# DMRobotSchematic.net
KiCad netlist of a schematic drawn in Altium Designer
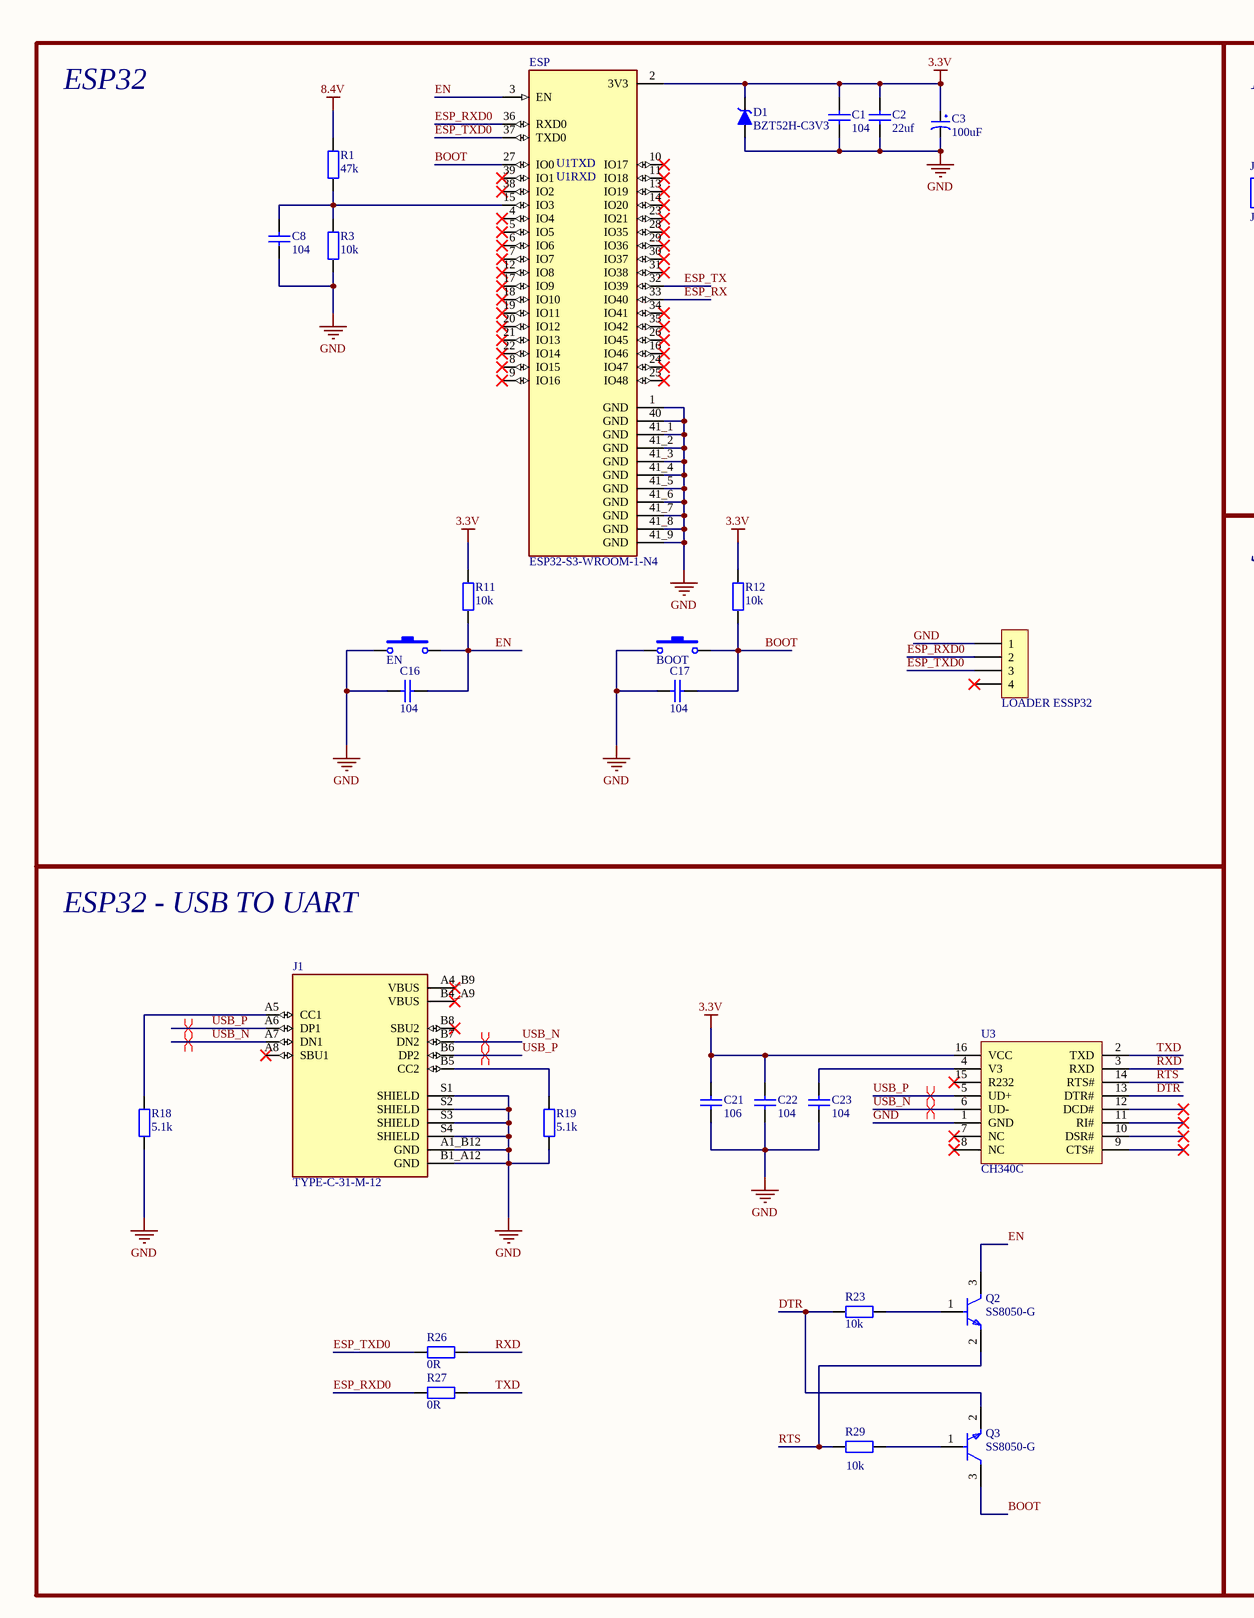
[diagram p0: DMRobotSchematic.SchDoc, left]
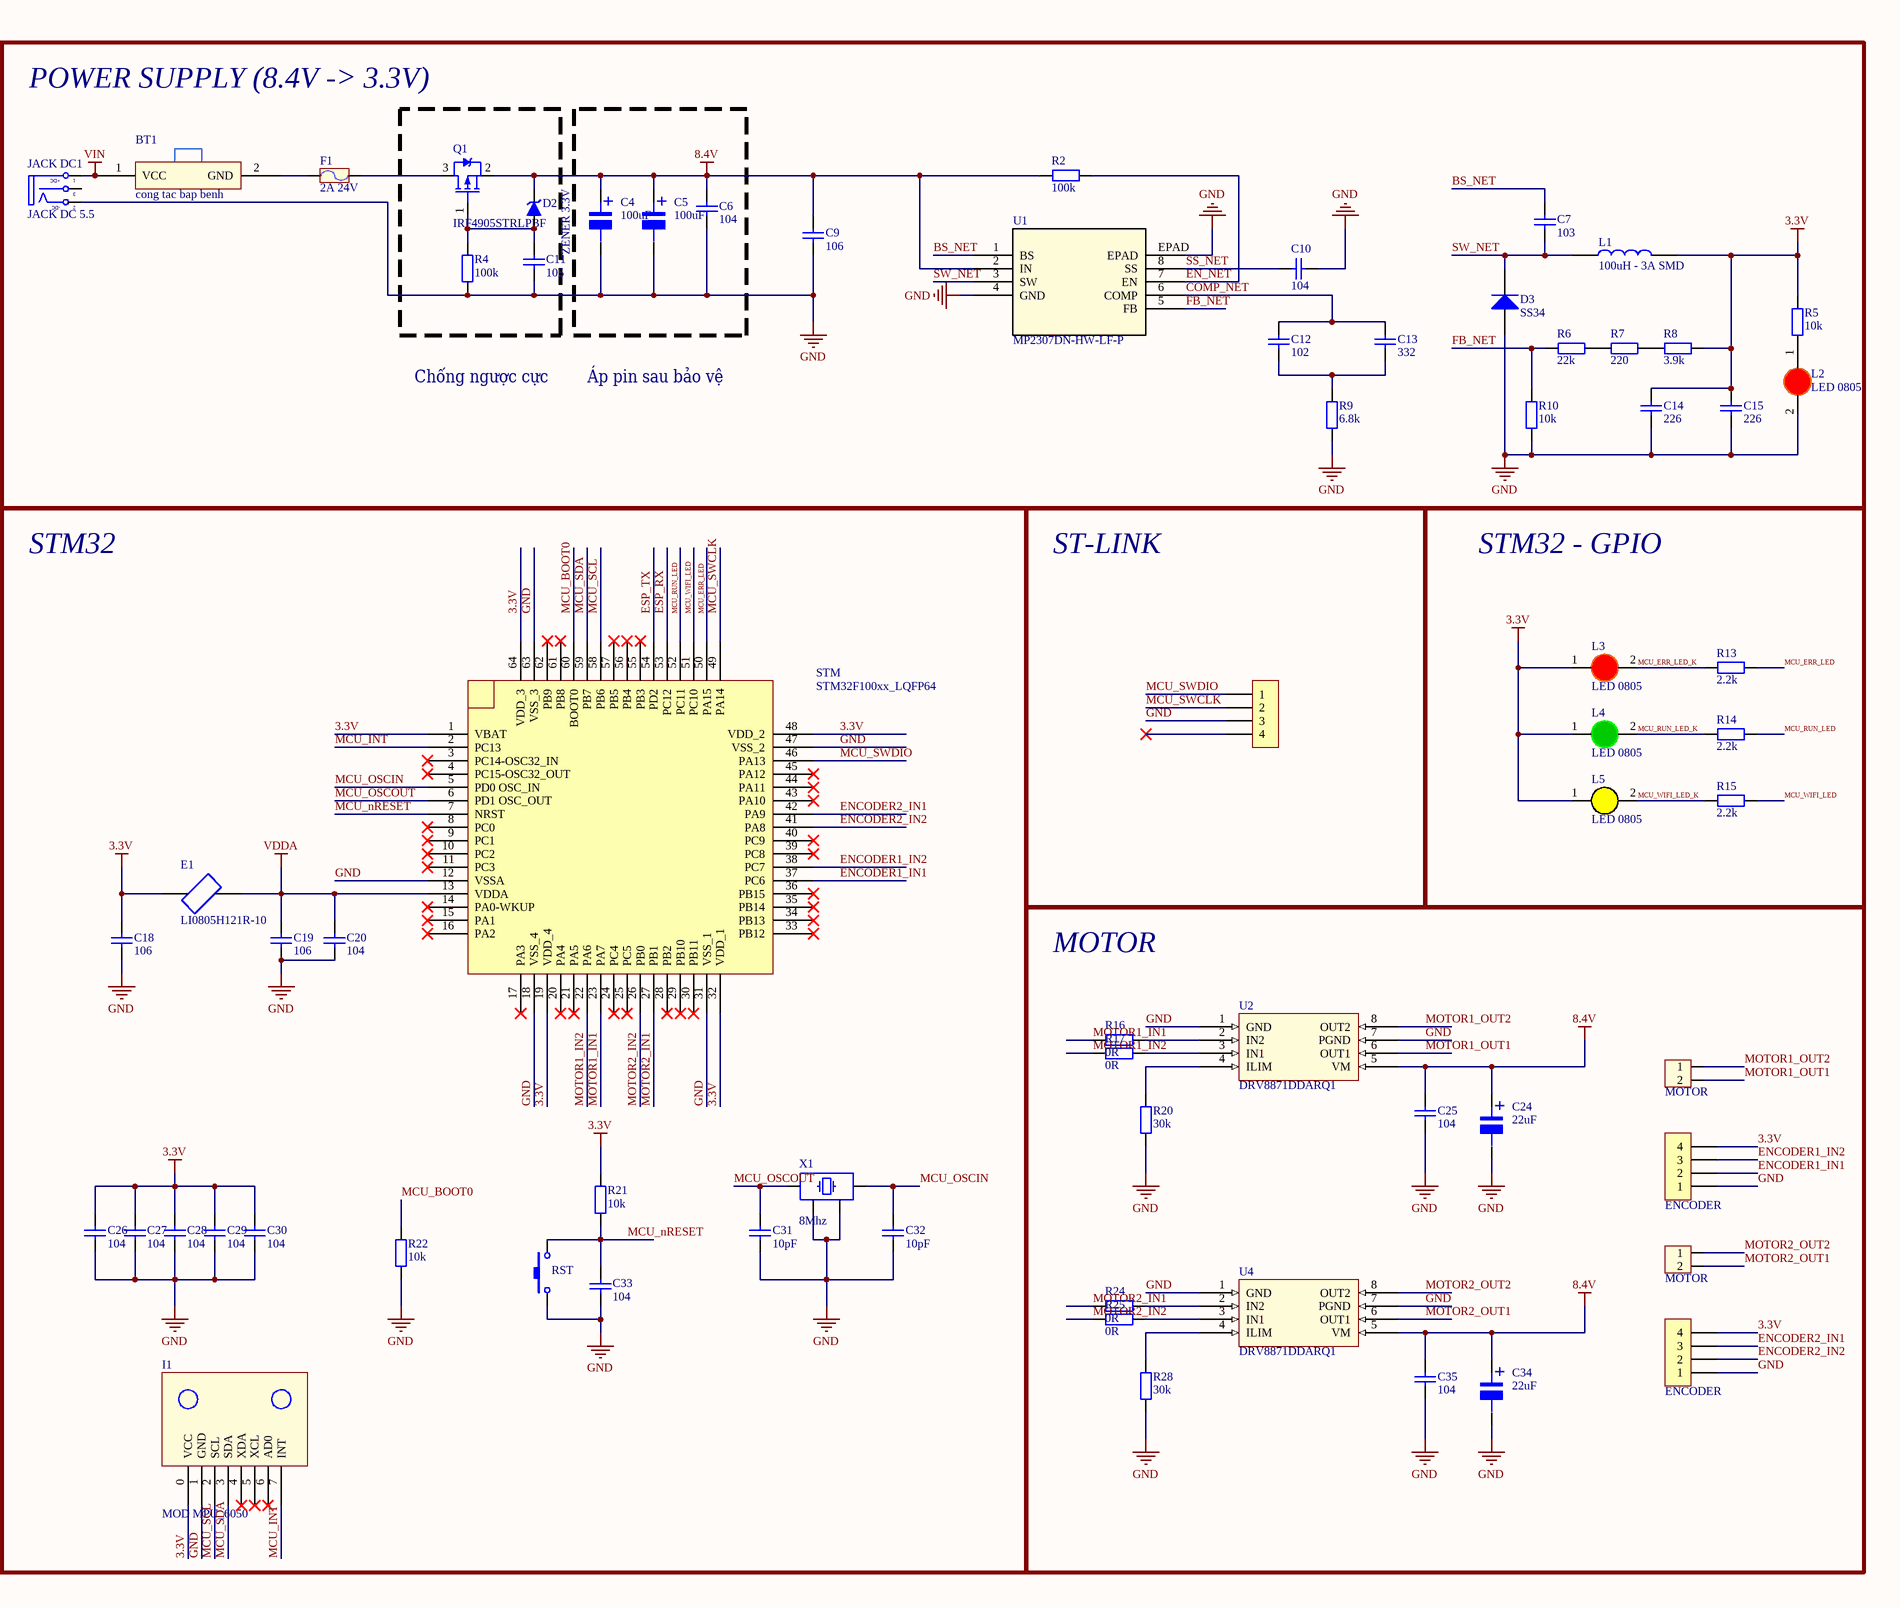
[diagram p1: DMRobotSchematic.SchDoc, right]

(export (version "E")
  (design (tool "Eeschema 10.0.6"))
  (components
    (comp (ref "BOOT")
      (value "Nut Nhan 2 Chan SMD 3x6x2.5")
      (footprint "Nut Nhan 2 Chan SMD 3x6x2.5")
      (libsource (lib "Prj_ArduinoUno_Khanh") (part "Nut Nhan 2 Chan SMD 3x6x2.5"))
    )
    (comp (ref "BT1")
      (value "cong tac bap benh")
      (footprint "CONG TAC BAP BENH")
      (libsource (lib "POWER_BOARD_FINAL") (part "cong tac bap benh"))
    )
    (comp (ref "C1")
      (value "104")
      (footprint "tu 0805")
      (description "Dán")
      (libsource (lib "Altium_Lib_by_KhueNguyenCreator") (part "Tu 0805 104 50V 10%"))
    )
    (comp (ref "C2")
      (value "22uf")
      (footprint "tu 0805")
      (description "Dán")
      (libsource (lib "Altium_Lib_by_KhueNguyenCreator") (part "Tu 0805 222 50V 10%"))
    )
    (comp (ref "C3")
      (value "100uF")
      (footprint "tu tantalum smd7343")
      (description "Dán")
      (libsource (lib "Altium_Lib_by_KhueNguyenCreator") (part "Tu tantalum 100uF 50V SMD7343"))
    )
    (comp (ref "C4")
      (value "100uF")
      (footprint "tu nhom 6.3 (d)")
      (description "Dán")
      (libsource (lib "Altium_Lib_by_KhueNguyenCreator") (part "Tu Nhom 100uF 25V"))
    )
    (comp (ref "C5")
      (value "100uF")
      (footprint "tu nhom 6.3 (d)")
      (description "Dán")
      (libsource (lib "Altium_Lib_by_KhueNguyenCreator") (part "Tu Nhom 100uF 25V"))
    )
    (comp (ref "C6")
      (value "104")
      (footprint "tu 0805")
      (description "Dán")
      (libsource (lib "Altium_Lib_by_KhueNguyenCreator") (part "Tu 0805 104 50V 10%"))
    )
    (comp (ref "C7")
      (value "103")
      (footprint "tu 0805")
      (description "Dán")
      (libsource (lib "Altium_Lib_by_KhueNguyenCreator") (part "Tu 0805 104 50V 10%"))
    )
    (comp (ref "C8")
      (value "104")
      (footprint "tu 0805")
      (description "Dán")
      (libsource (lib "Altium_Lib_by_KhueNguyenCreator") (part "Tu 0805 104 50V 10%"))
    )
    (comp (ref "C9")
      (value "106")
      (footprint "tu 0805")
      (description "Dán")
      (libsource (lib "Altium_Lib_by_KhueNguyenCreator") (part "Tu 0805 106 16V 10%"))
    )
    (comp (ref "C10")
      (value "104")
      (footprint "tu 0805")
      (description "Dán")
      (libsource (lib "Altium_Lib_by_KhueNguyenCreator") (part "Tu 0805 104 50V 10%"))
    )
    (comp (ref "C11")
      (value "105")
      (footprint "tu 0805")
      (description "Dán")
      (libsource (lib "Altium_Lib_by_KhueNguyenCreator") (part "Tu 0805 105 50V 10%"))
    )
    (comp (ref "C12")
      (value "102")
      (footprint "tu 0805")
      (description "Dán")
      (libsource (lib "Altium_Lib_by_KhueNguyenCreator") (part "Tu 0805 102 50V 10%"))
    )
    (comp (ref "C13")
      (value "332")
      (footprint "tu 0805")
      (description "Dán")
      (libsource (lib "Altium_Lib_by_KhueNguyenCreator") (part "Tu 0805 332 50V 10%"))
    )
    (comp (ref "C14")
      (value "226")
      (footprint "tu 1206")
      (description "Dán")
      (libsource (lib "Altium_Lib_by_KhueNguyenCreator") (part "Tu 1206 226 16V 20%"))
    )
    (comp (ref "C15")
      (value "226")
      (footprint "tu 1206")
      (description "Dán")
      (libsource (lib "Altium_Lib_by_KhueNguyenCreator") (part "Tu 1206 226 16V 20%"))
    )
    (comp (ref "C16")
      (value "104")
      (footprint "tu 0805")
      (description "Dán")
      (libsource (lib "Altium_Lib_by_KhueNguyenCreator") (part "Tu 0805 104 50V 10%"))
    )
    (comp (ref "C17")
      (value "104")
      (footprint "tu 0805")
      (description "Dán")
      (libsource (lib "Altium_Lib_by_KhueNguyenCreator") (part "Tu 0805 104 50V 10%"))
    )
    (comp (ref "C18")
      (value "106")
      (footprint "tu 0805")
      (description "Dán")
      (libsource (lib "Altium_Lib_by_KhueNguyenCreator") (part "Tu 0805 106 16V 10%"))
    )
    (comp (ref "C19")
      (value "106")
      (footprint "tu 0805")
      (description "Dán")
      (libsource (lib "Altium_Lib_by_KhueNguyenCreator") (part "Tu 0805 106 16V 10%"))
    )
    (comp (ref "C20")
      (value "104")
      (footprint "tu 0805")
      (description "Dán")
      (libsource (lib "Altium_Lib_by_KhueNguyenCreator") (part "Tu 0805 104 50V 10%"))
    )
    (comp (ref "C21")
      (value "106")
      (footprint "tu 0805")
      (description "Dán")
      (libsource (lib "Altium_Lib_by_KhueNguyenCreator") (part "Tu 0805 106 16V 10%"))
    )
    (comp (ref "C22")
      (value "104")
      (footprint "tu 0805")
      (description "Dán")
      (libsource (lib "Altium_Lib_by_KhueNguyenCreator") (part "Tu 0805 104 50V 10%"))
    )
    (comp (ref "C23")
      (value "104")
      (footprint "tu 0805")
      (description "Dán")
      (libsource (lib "Altium_Lib_by_KhueNguyenCreator") (part "Tu 0805 104 50V 10%"))
    )
    (comp (ref "C24")
      (value "22uF")
      (footprint "tu nhom 6.3 (D)")
      (description "Dán")
      (libsource (lib "Altium_Lib_by_KhueNguyenCreator") (part "Tu Nhom 22uF 25V"))
    )
    (comp (ref "C25")
      (value "104")
      (footprint "tu 0805")
      (description "Dán")
      (libsource (lib "Altium_Lib_by_KhueNguyenCreator") (part "Tu 0805 104 50V 10%"))
    )
    (comp (ref "C26")
      (value "104")
      (footprint "tu 0805")
      (description "Dán")
      (libsource (lib "Altium_Lib_by_KhueNguyenCreator") (part "Tu 0805 104 50V 10%"))
    )
    (comp (ref "C27")
      (value "104")
      (footprint "tu 0805")
      (description "Dán")
      (libsource (lib "Altium_Lib_by_KhueNguyenCreator") (part "Tu 0805 104 50V 10%"))
    )
    (comp (ref "C28")
      (value "104")
      (footprint "tu 0805")
      (description "Dán")
      (libsource (lib "Altium_Lib_by_KhueNguyenCreator") (part "Tu 0805 104 50V 10%"))
    )
    (comp (ref "C29")
      (value "104")
      (footprint "tu 0805")
      (description "Dán")
      (libsource (lib "Altium_Lib_by_KhueNguyenCreator") (part "Tu 0805 104 50V 10%"))
    )
    (comp (ref "C30")
      (value "104")
      (footprint "tu 0805")
      (description "Dán")
      (libsource (lib "Altium_Lib_by_KhueNguyenCreator") (part "Tu 0805 104 50V 10%"))
    )
    (comp (ref "C31")
      (value "10pF")
      (footprint "tu 0805")
      (description "Dán")
      (libsource (lib "Altium_Lib_by_KhueNguyenCreator") (part "Tu 0805 10pF 50V 10%"))
    )
    (comp (ref "C32")
      (value "10pF")
      (footprint "tu 0805")
      (description "Dán")
      (libsource (lib "Altium_Lib_by_KhueNguyenCreator") (part "Tu 0805 10pF 50V 10%"))
    )
    (comp (ref "C33")
      (value "104")
      (footprint "tu 0805")
      (description "Dán")
      (libsource (lib "Altium_Lib_by_KhueNguyenCreator") (part "Tu 0805 104 50V 10%"))
    )
    (comp (ref "C34")
      (value "22uF")
      (footprint "tu nhom 6.3 (D)")
      (description "Dán")
      (libsource (lib "Altium_Lib_by_KhueNguyenCreator") (part "Tu Nhom 22uF 25V"))
    )
    (comp (ref "C35")
      (value "104")
      (footprint "tu 0805")
      (description "Dán")
      (libsource (lib "Altium_Lib_by_KhueNguyenCreator") (part "Tu 0805 104 50V 10%"))
    )
    (comp (ref "D1")
      (value "BZT52H-C3V3")
      (footprint "SOD123")
      (description "Zener Diode")
      (libsource (lib "chipfc_libs") (part "Diode Zener"))
    )
    (comp (ref "D2")
      (value "ZENER 3.3V")
      (footprint "SOD123")
      (description "Zener Diode")
      (libsource (lib "chipfc_libs") (part "Diode Zener"))
    )
    (comp (ref "D3")
      (value "SS34")
      (footprint "DIODE SMA")
      (description "Dán")
      (libsource (lib "Altium_Lib_by_KhueNguyenCreator") (part "Diode SS34 ( 1N5822 )"))
    )
    (comp (ref "E1")
      (value "LI0805H121R-10")
      (footprint "FB_LI0805H121R-10")
      (fields (field (name "MF") "Laird"))
      (libsource (lib "MCU_FINAL") (part "LI0805H121R-10"))
    )
    (comp (ref "EN")
      (value "Nut Nhan 2 Chan SMD 3x6x2.5")
      (footprint "Nut Nhan 2 Chan SMD 3x6x2.5")
      (libsource (lib "Prj_ArduinoUno_Khanh") (part "Nut Nhan 2 Chan SMD 3x6x2.5"))
    )
    (comp (ref "ENC1")
      (value "ENCODER")
      (footprint "XH2.54M-4")
      (description "Cắm")
      (libsource (lib "") (part "Header 4P 2.54 Duc Thang_1"))
    )
    (comp (ref "ENC2")
      (value "ENCODER")
      (footprint "XH2.54M-4")
      (description "Cắm")
      (libsource (lib "") (part "Header 4P 2.54 Duc Thang_1"))
    )
    (comp (ref "ESP")
      (value "ESP32-S3-WROOM-1-N4")
      (footprint "XCVR_ESP32-S3-WROOM-1-N4")
      (fields (field (name "MF") "{'manufacturer': u'Espressif Systems'}"))
      (libsource (lib "ESP32-S3-WROOM-1-N4") (part "ESP32-S3-WROOM-1-N4"))
    )
    (comp (ref "ESP_FLASH")
      (value "LOADER ESSP32")
      (footprint "XH2.54M-4")
      (description "Cắm")
      (libsource (lib "Altium_Lib_by_KhueNguyenCreator") (part "Header 4P 2.54 Duc Thang"))
    )
    (comp (ref "F1")
      (value "2A 24V")
      (footprint "Cau chi tu phuc hoi 2A 24V SMD1812")
      (description "2A 24V SMD1812")
      (libsource (lib "Altium_Lib_by_KhueNguyenCreator") (part "Cau chi tu phuc hoi 2A 24V SMD1812"))
    )
    (comp (ref "I1")
      (value "MOD MPU_6050")
      (footprint "MOD MPU-6050")
      (libsource (lib "Altium_Lib_by_KhueNguyenCreator") (part "MOD MPU_6050"))
    )
    (comp (ref "J1")
      (value "TYPE-C-31-M-12")
      (footprint "HRO_TYPE-C-31-M-12")
      (description "USB Connectors 24 Receptacle 1 8.94*7.3mm RoHS")
      (fields (field (name "MF") "HRO Electronics Co., Ltd."))
      (libsource (lib "TYPE-C-31-M-12") (part "TYPE-C-31-M-12"))
    )
    (comp (ref "JACK DC1")
      (value "JACK DC 5.5")
      (footprint "JACK DC 5.5")
      (libsource (lib "Altium_Lib_by_KhueNguyenCreator") (part "JACK DC 5.5"))
    )
    (comp (ref "L1")
      (value "100uH - 3A SMD")
      (footprint "Cuon Cam 12x12x10")
      (description "Dán")
      (libsource (lib "Altium_Lib_by_KhueNguyenCreator") (part "CUON CAM 100uH SMD"))
    )
    (comp (ref "L2")
      (value "LED 0805")
      (footprint "LED-0805-Red")
      (description "Dán")
      (libsource (lib "Altium_Lib_by_KhueNguyenCreator") (part "LED 0805 Do"))
    )
    (comp (ref "L3")
      (value "LED 0805")
      (footprint "LED-0805-Red")
      (description "Dán")
      (libsource (lib "Altium_Lib_by_KhueNguyenCreator") (part "LED 0805 Do"))
    )
    (comp (ref "L4")
      (value "LED 0805")
      (footprint "LED-0805-Green")
      (description "Dán")
      (libsource (lib "Altium_Lib_by_KhueNguyenCreator") (part "LED 0805 Xanh La"))
    )
    (comp (ref "L5")
      (value "LED 0805")
      (footprint "LED-0805-Yellow")
      (description "Dán")
      (libsource (lib "Altium_Lib_by_KhueNguyenCreator") (part "LED 0805 Vang"))
    )
    (comp (ref "M1")
      (value "MOTOR")
      (footprint "XH2.54M-2")
      (description "Cắm")
      (libsource (lib "Altium_Lib_by_KhueNguyenCreator") (part "Header 2P 2.54 Duc Thang"))
    )
    (comp (ref "M2")
      (value "MOTOR")
      (footprint "XH2.54M-2")
      (description "Cắm")
      (libsource (lib "Altium_Lib_by_KhueNguyenCreator") (part "Header 2P 2.54 Duc Thang"))
    )
    (comp (ref "Q1")
      (value "IRF4905STRLPBF")
      (footprint "TO-263 (D2PAK)")
      (description "Mosfet P")
      (libsource (lib "POWER_BOARD_FINAL") (part "Mosfet P"))
    )
    (comp (ref "Q2")
      (value "SS8050-G")
      (footprint "FP-SS8050-G-MFG")
      (description "NPN TRANSISTOR 1.5A 40V SOT-23 R")
      (libsource (lib "Altium Content Vault") (part "2a1388f82443b098dcd57d24ac7632d"))
    )
    (comp (ref "Q3")
      (value "SS8050-G")
      (footprint "FP-SS8050-G-MFG")
      (description "NPN TRANSISTOR 1.5A 40V SOT-23 R")
      (libsource (lib "Altium Content Vault") (part "2a1388f82443b098dcd57d24ac7632d"))
    )
    (comp (ref "R1")
      (value "47k")
      (footprint "tro smd 0603")
      (description "Dán")
      (libsource (lib "Altium_Lib_by_KhueNguyenCreator") (part "Tro 0603 5% 47k"))
    )
    (comp (ref "R2")
      (value "100k")
      (footprint "tro smd 0805")
      (description "Dán")
      (libsource (lib "Altium_Lib_by_KhueNguyenCreator") (part "Tro 0805 5% 100k"))
    )
    (comp (ref "R3")
      (value "10k")
      (footprint "tro smd 0805")
      (description "Dán")
      (libsource (lib "Altium_Lib_by_KhueNguyenCreator") (part "Tro 0805 5% 10k"))
    )
    (comp (ref "R4")
      (value "100k")
      (footprint "tro smd 0805")
      (description "Dán")
      (libsource (lib "Altium_Lib_by_KhueNguyenCreator") (part "Tro 0805 5% 100k"))
    )
    (comp (ref "R5")
      (value "10k")
      (footprint "tro smd 0805")
      (description "Dán")
      (libsource (lib "Altium_Lib_by_KhueNguyenCreator") (part "Tro 0805 5% 10k"))
    )
    (comp (ref "R6")
      (value "22k")
      (footprint "tro smd 0805")
      (description "Dán")
      (libsource (lib "Altium_Lib_by_KhueNguyenCreator") (part "Tro 0805 5% 22k"))
    )
    (comp (ref "R7")
      (value "220")
      (footprint "tro smd 0805")
      (description "Dán")
      (libsource (lib "Altium_Lib_by_KhueNguyenCreator") (part "Tro 0805 5% 220R"))
    )
    (comp (ref "R8")
      (value "3.9k")
      (footprint "Tro SMD 0805")
      (description "Dán")
      (libsource (lib "Altium_Lib_by_KhueNguyenCreator") (part "Tro 0805 5% 3.9k"))
    )
    (comp (ref "R9")
      (value "6.8k")
      (footprint "tro smd 0805")
      (description "Dán")
      (libsource (lib "Altium_Lib_by_KhueNguyenCreator") (part "Tro 0805 5% 6.8k"))
    )
    (comp (ref "R10")
      (value "10k")
      (footprint "tro smd 0805")
      (description "Dán")
      (libsource (lib "Altium_Lib_by_KhueNguyenCreator") (part "Tro 0805 5% 10k"))
    )
    (comp (ref "R11")
      (value "10k")
      (footprint "tro smd 0805")
      (description "Dán")
      (libsource (lib "Altium_Lib_by_KhueNguyenCreator") (part "Tro 0805 5% 10k"))
    )
    (comp (ref "R12")
      (value "10k")
      (footprint "tro smd 0805")
      (description "Dán")
      (libsource (lib "Altium_Lib_by_KhueNguyenCreator") (part "Tro 0805 5% 10k"))
    )
    (comp (ref "R13")
      (value "2.2k")
      (footprint "tro smd 0805")
      (description "Dán")
      (libsource (lib "Altium_Lib_by_KhueNguyenCreator") (part "Tro 0805 5% 2.2k"))
    )
    (comp (ref "R14")
      (value "2.2k")
      (footprint "tro smd 0805")
      (description "Dán")
      (libsource (lib "Altium_Lib_by_KhueNguyenCreator") (part "Tro 0805 5% 2.2k"))
    )
    (comp (ref "R15")
      (value "2.2k")
      (footprint "tro smd 0805")
      (description "Dán")
      (libsource (lib "Altium_Lib_by_KhueNguyenCreator") (part "Tro 0805 5% 2.2k"))
    )
    (comp (ref "R16")
      (value "0R")
      (footprint "tro smd 0805")
      (description "Dán")
      (libsource (lib "Altium_Lib_by_KhueNguyenCreator") (part "Tro 0805 5% 0R"))
    )
    (comp (ref "R17")
      (value "0R")
      (footprint "tro smd 0805")
      (description "Dán")
      (libsource (lib "Altium_Lib_by_KhueNguyenCreator") (part "Tro 0805 5% 0R"))
    )
    (comp (ref "R18")
      (value "5.1k")
      (footprint "tro smd 0805")
      (description "Dán")
      (libsource (lib "Altium_Lib_by_KhueNguyenCreator") (part "Tro 0805 1% 5.1k"))
    )
    (comp (ref "R19")
      (value "5.1k")
      (footprint "tro smd 0805")
      (description "Dán")
      (libsource (lib "Altium_Lib_by_KhueNguyenCreator") (part "Tro 0805 1% 5.1k"))
    )
    (comp (ref "R20")
      (value "30k")
      (footprint "tro smd 0805")
      (description "Dán")
      (libsource (lib "Altium_Lib_by_KhueNguyenCreator") (part "Tro 0805 5% 30k"))
    )
    (comp (ref "R21")
      (value "10k")
      (footprint "tro smd 0805")
      (description "Dán")
      (libsource (lib "Altium_Lib_by_KhueNguyenCreator") (part "Tro 0805 5% 10k"))
    )
    (comp (ref "R22")
      (value "10k")
      (footprint "tro smd 0805")
      (description "Dán")
      (libsource (lib "Altium_Lib_by_KhueNguyenCreator") (part "Tro 0805 5% 10k"))
    )
    (comp (ref "R23")
      (value "10k")
      (footprint "tro smd 0805")
      (description "Dán")
      (libsource (lib "Altium_Lib_by_KhueNguyenCreator") (part "Tro 0805 5% 10k"))
    )
    (comp (ref "R24")
      (value "0R")
      (footprint "tro smd 0805")
      (description "Dán")
      (libsource (lib "Altium_Lib_by_KhueNguyenCreator") (part "Tro 0805 5% 0R"))
    )
    (comp (ref "R25")
      (value "0R")
      (footprint "tro smd 0805")
      (description "Dán")
      (libsource (lib "Altium_Lib_by_KhueNguyenCreator") (part "Tro 0805 5% 0R"))
    )
    (comp (ref "R26")
      (value "0R")
      (footprint "tro smd 0805")
      (description "Dán")
      (libsource (lib "Altium_Lib_by_KhueNguyenCreator") (part "Tro 0805 5% 0R"))
    )
    (comp (ref "R27")
      (value "0R")
      (footprint "tro smd 0805")
      (description "Dán")
      (libsource (lib "Altium_Lib_by_KhueNguyenCreator") (part "Tro 0805 5% 0R"))
    )
    (comp (ref "R28")
      (value "30k")
      (footprint "tro smd 0805")
      (description "Dán")
      (libsource (lib "Altium_Lib_by_KhueNguyenCreator") (part "Tro 0805 5% 30k"))
    )
    (comp (ref "R29")
      (value "10k")
      (footprint "tro smd 0805")
      (description "Dán")
      (libsource (lib "Altium_Lib_by_KhueNguyenCreator") (part "Tro 0805 5% 10k"))
    )
    (comp (ref "RST")
      (value "Nut Nhan 2 Chan SMD 3x6x2.5")
      (footprint "Nut Nhan 2 Chan SMD 3x6x2.5")
      (libsource (lib "Prj_ArduinoUno_Khanh") (part "Nut Nhan 2 Chan SMD 3x6x2.5"))
    )
    (comp (ref "STM")
      (value "STM32F100xx_LQFP64")
      (footprint "STM32_LQFP64")
      (libsource (lib "Altium_Lib_by_KhueNguyenCreator") (part "STM32F100xx_LQFP64"))
    )
    (comp (ref "STM_FLASH")
      (value "Header 4P 2.54 Duc Thang")
      (footprint "XH2.54M-4")
      (description "Cắm")
      (libsource (lib "Altium_Lib_by_KhueNguyenCreator") (part "Header 4P 2.54 Duc Thang"))
    )
    (comp (ref "U1")
      (value "MP2307DN-HW-LF-P")
      (footprint "IC8_MP2307_MNP")
      (description "3A 23V 340KHz Synchronous Rectified Step-Down Converter")
      (fields (field (name "COPYRIGHT") "Copyright (C) 2025 Ultra Librarian. All rights reserved."))
      (libsource (lib "POWER_BOARD_FINAL") (part "MP2307DN-HW-LF-P"))
    )
    (comp (ref "U2")
      (value "DRV8871DDARQ1")
      (footprint "SOIC8_50_328_25X90_SMT")
      (description "Unipolar Motor Driver NMOS PWM 8-SO PowerPad")
      (fields (field (name "MANUFACTURER") "Texas Instruments"))
      (libsource (lib "Altium_Lib_by_KhueNguyenCreator") (part "IC_DRV8871DDARQ1"))
    )
    (comp (ref "U3")
      (value "CH340C")
      (footprint "SOIC16_50_284_25X90_SMT")
      (description "USB Bridge, USB to UART USB 2.0 UART Interface")
      (fields (field (name "MANUFACTURER") "Olimex"))
      (libsource (lib "Altium_Lib_by_KhueNguyenCreator") (part "IC_CH340C"))
    )
    (comp (ref "U4")
      (value "DRV8871DDARQ1")
      (footprint "SOIC8_50_328_25X90_SMT")
      (description "Unipolar Motor Driver NMOS PWM 8-SO PowerPad")
      (fields (field (name "MANUFACTURER") "Texas Instruments"))
      (libsource (lib "Altium_Lib_by_KhueNguyenCreator") (part "IC_DRV8871DDARQ1"))
    )
    (comp (ref "X1")
      (value "8Mhz")
      (footprint "XTAL_3225")
      (description "Crystal SMD 24MHz 10PPM 7pF 3225")
      (fields
        (field (name "MANUFACTURER") "Epson")
        (field (name "MANUFACTURER PART NUMBER") "TSX-3225 24.0000MF15X-AC")
      )
      (libsource (lib "MCU_FINAL") (part "TSX-3225_24.0000MF15X-AC"))
    )
  )
  (nets
    (net (code "1") (name "/BOOT") (class "Default")
      (node (ref "BOOT") (pin "2") (pinfunction "2_2") (pintype "passive"))
      (node (ref "C17") (pin "2") (pinfunction "2_2") (pintype "passive"))
      (node (ref "ESP") (pin "27") (pinfunction "IO0_27") (pintype "bidirectional"))
      (node (ref "Q3") (pin "3") (pinfunction "C_3") (pintype "passive"))
      (node (ref "R12") (pin "1") (pinfunction "1_1") (pintype "passive"))
    )
    (net (code "2") (name "/BS_NET") (class "Default")
      (node (ref "C7") (pin "1") (pinfunction "1_1") (pintype "passive"))
      (node (ref "U1") (pin "1") (pinfunction "BS_1") (pintype "passive"))
    )
    (net (code "3") (name "/COMP_NET") (class "Default")
      (node (ref "C12") (pin "1") (pinfunction "1_1") (pintype "passive"))
      (node (ref "C13") (pin "1") (pinfunction "1_1") (pintype "passive"))
      (node (ref "U1") (pin "6") (pinfunction "COMP_6") (pintype "passive"))
    )
    (net (code "4") (name "/DTR") (class "Default")
      (node (ref "Q3") (pin "2") (pinfunction "E_2") (pintype "passive"))
      (node (ref "R23") (pin "1") (pinfunction "1_1") (pintype "passive"))
      (node (ref "U3") (pin "13") (pinfunction "DTR#_13") (pintype "passive"))
    )
    (net (code "5") (name "/EN") (class "Default")
      (node (ref "C16") (pin "2") (pinfunction "2_2") (pintype "passive"))
      (node (ref "EN") (pin "2") (pinfunction "2_2") (pintype "passive"))
      (node (ref "ESP") (pin "3") (pinfunction "EN_3") (pintype "input"))
      (node (ref "Q2") (pin "3") (pinfunction "C_3") (pintype "passive"))
      (node (ref "R11") (pin "1") (pinfunction "1_1") (pintype "passive"))
    )
    (net (code "6") (name "/ENCODER1_IN1") (class "Default")
      (node (ref "ENC1") (pin "2") (pinfunction "2_2") (pintype "passive"))
      (node (ref "STM") (pin "37") (pinfunction "PC6_37") (pintype "passive"))
    )
    (net (code "7") (name "/ENCODER1_IN2") (class "Default")
      (node (ref "ENC1") (pin "3") (pinfunction "3_3") (pintype "passive"))
      (node (ref "STM") (pin "38") (pinfunction "PC7_38") (pintype "passive"))
    )
    (net (code "8") (name "/ENCODER2_IN1") (class "Default")
      (node (ref "ENC2") (pin "3") (pinfunction "3_3") (pintype "passive"))
      (node (ref "STM") (pin "42") (pinfunction "PA9_42") (pintype "passive"))
    )
    (net (code "9") (name "/ENCODER2_IN2") (class "Default")
      (node (ref "ENC2") (pin "2") (pinfunction "2_2") (pintype "passive"))
      (node (ref "STM") (pin "41") (pinfunction "PA8_41") (pintype "passive"))
    )
    (net (code "10") (name "/EN_NET") (class "Default")
      (node (ref "R2") (pin "2") (pinfunction "2_2") (pintype "passive"))
      (node (ref "U1") (pin "7") (pinfunction "EN_7") (pintype "passive"))
    )
    (net (code "11") (name "/ESP_RX") (class "Default")
      (node (ref "ESP") (pin "33") (pinfunction "IO40_33") (pintype "bidirectional"))
      (node (ref "STM") (pin "53") (pinfunction "PC12_53") (pintype "passive"))
    )
    (net (code "12") (name "/ESP_RXD0") (class "Default")
      (node (ref "ESP") (pin "36") (pinfunction "RXD0_36") (pintype "bidirectional"))
      (node (ref "ESP_FLASH") (pin "2") (pinfunction "2_2") (pintype "passive"))
      (node (ref "R27") (pin "1") (pinfunction "1_1") (pintype "passive"))
    )
    (net (code "13") (name "/ESP_TX") (class "Default")
      (node (ref "ESP") (pin "32") (pinfunction "IO39_32") (pintype "bidirectional"))
      (node (ref "STM") (pin "54") (pinfunction "PD2_54") (pintype "passive"))
    )
    (net (code "14") (name "/ESP_TXD0") (class "Default")
      (node (ref "ESP") (pin "37") (pinfunction "TXD0_37") (pintype "bidirectional"))
      (node (ref "ESP_FLASH") (pin "3") (pinfunction "3_3") (pintype "passive"))
      (node (ref "R26") (pin "1") (pinfunction "1_1") (pintype "passive"))
    )
    (net (code "15") (name "/FB_NET") (class "Default")
      (node (ref "R10") (pin "1") (pinfunction "1_1") (pintype "passive"))
      (node (ref "R6") (pin "1") (pinfunction "1_1") (pintype "passive"))
      (node (ref "U1") (pin "5") (pinfunction "FB_5") (pintype "passive"))
    )
    (net (code "16") (name "/MCU_BOOT0") (class "Default")
      (node (ref "R22") (pin "1") (pinfunction "1_1") (pintype "passive"))
      (node (ref "STM") (pin "60") (pinfunction "BOOT0_60") (pintype "passive"))
    )
    (net (code "17") (name "/MCU_ERR_LED") (class "Default")
      (node (ref "R13") (pin "2") (pinfunction "2_2") (pintype "passive"))
      (node (ref "STM") (pin "50") (pinfunction "PA15_50") (pintype "passive"))
    )
    (net (code "18") (name "/MCU_ERR_LED_K") (class "Default")
      (node (ref "L3") (pin "2") (pinfunction "K_2") (pintype "passive"))
      (node (ref "R13") (pin "1") (pinfunction "1_1") (pintype "passive"))
    )
    (net (code "19") (name "/MCU_INT") (class "Default")
      (node (ref "I1") (pin "7") (pinfunction "INT_7") (pintype "passive"))
      (node (ref "STM") (pin "2") (pinfunction "PC13_2") (pintype "passive"))
    )
    (net (code "20") (name "/MCU_OSCIN") (class "Default")
      (node (ref "C32") (pin "1") (pinfunction "1_1") (pintype "passive"))
      (node (ref "STM") (pin "5") (pinfunction "PD0_OSC_IN_5") (pintype "passive"))
      (node (ref "X1") (pin "3") (pinfunction "3_3") (pintype "passive"))
    )
    (net (code "21") (name "/MCU_OSCOUT") (class "Default")
      (node (ref "C31") (pin "1") (pinfunction "1_1") (pintype "passive"))
      (node (ref "STM") (pin "6") (pinfunction "PD1_OSC_OUT_6") (pintype "passive"))
      (node (ref "X1") (pin "1") (pinfunction "1_1") (pintype "passive"))
    )
    (net (code "22") (name "/MCU_RUN_LED") (class "Default")
      (node (ref "R14") (pin "2") (pinfunction "2_2") (pintype "passive"))
      (node (ref "STM") (pin "52") (pinfunction "PC11_52") (pintype "passive"))
    )
    (net (code "23") (name "/MCU_RUN_LED_K") (class "Default")
      (node (ref "L4") (pin "2") (pinfunction "K_2") (pintype "passive"))
      (node (ref "R14") (pin "1") (pinfunction "1_1") (pintype "passive"))
    )
    (net (code "24") (name "/MCU_SCL") (class "Default")
      (node (ref "I1") (pin "2") (pinfunction "SCL_2") (pintype "passive"))
      (node (ref "STM") (pin "58") (pinfunction "PB6_58") (pintype "passive"))
    )
    (net (code "25") (name "/MCU_SDA") (class "Default")
      (node (ref "I1") (pin "3") (pinfunction "SDA_3") (pintype "passive"))
      (node (ref "STM") (pin "59") (pinfunction "PB7_59") (pintype "passive"))
    )
    (net (code "26") (name "/MCU_SWCLK") (class "Default")
      (node (ref "STM") (pin "49") (pinfunction "PA14_49") (pintype "passive"))
      (node (ref "STM_FLASH") (pin "2") (pinfunction "2_2") (pintype "passive"))
    )
    (net (code "27") (name "/MCU_SWDIO") (class "Default")
      (node (ref "STM") (pin "46") (pinfunction "PA13_46") (pintype "passive"))
      (node (ref "STM_FLASH") (pin "1") (pinfunction "1_1") (pintype "passive"))
    )
    (net (code "28") (name "/MCU_WIFI_LED") (class "Default")
      (node (ref "R15") (pin "2") (pinfunction "2_2") (pintype "passive"))
      (node (ref "STM") (pin "51") (pinfunction "PC10_51") (pintype "passive"))
    )
    (net (code "29") (name "/MCU_WIFI_LED_K") (class "Default")
      (node (ref "L5") (pin "2") (pinfunction "K_2") (pintype "passive"))
      (node (ref "R15") (pin "1") (pinfunction "1_1") (pintype "passive"))
    )
    (net (code "30") (name "/MCU_nRESET") (class "Default")
      (node (ref "C33") (pin "2") (pinfunction "2_2") (pintype "passive"))
      (node (ref "R21") (pin "2") (pinfunction "2_2") (pintype "passive"))
      (node (ref "RST") (pin "2") (pinfunction "2_2") (pintype "passive"))
      (node (ref "STM") (pin "7") (pinfunction "NRST_7") (pintype "passive"))
    )
    (net (code "31") (name "/MOTOR1_IN1") (class "Default")
      (node (ref "R16") (pin "1") (pinfunction "1_1") (pintype "passive"))
      (node (ref "STM") (pin "23") (pinfunction "PA7_23") (pintype "passive"))
    )
    (net (code "32") (name "/MOTOR1_IN2") (class "Default")
      (node (ref "R17") (pin "1") (pinfunction "1_1") (pintype "passive"))
      (node (ref "STM") (pin "22") (pinfunction "PA6_22") (pintype "passive"))
    )
    (net (code "33") (name "/MOTOR1_OUT1") (class "Default")
      (node (ref "M1") (pin "2") (pinfunction "2_2") (pintype "passive"))
      (node (ref "U2") (pin "6") (pinfunction "OUT1_6") (pintype "input"))
    )
    (net (code "34") (name "/MOTOR1_OUT2") (class "Default")
      (node (ref "M1") (pin "1") (pinfunction "1_1") (pintype "passive"))
      (node (ref "U2") (pin "8") (pinfunction "OUT2_8") (pintype "input"))
    )
    (net (code "35") (name "/MOTOR2_IN1") (class "Default")
      (node (ref "R24") (pin "1") (pinfunction "1_1") (pintype "passive"))
      (node (ref "STM") (pin "27") (pinfunction "PB1_27") (pintype "passive"))
    )
    (net (code "36") (name "/MOTOR2_IN2") (class "Default")
      (node (ref "R25") (pin "1") (pinfunction "1_1") (pintype "passive"))
      (node (ref "STM") (pin "26") (pinfunction "PB0_26") (pintype "passive"))
    )
    (net (code "37") (name "/MOTOR2_OUT1") (class "Default")
      (node (ref "M2") (pin "2") (pinfunction "2_2") (pintype "passive"))
      (node (ref "U4") (pin "6") (pinfunction "OUT1_6") (pintype "input"))
    )
    (net (code "38") (name "/MOTOR2_OUT2") (class "Default")
      (node (ref "M2") (pin "1") (pinfunction "1_1") (pintype "passive"))
      (node (ref "U4") (pin "8") (pinfunction "OUT2_8") (pintype "input"))
    )
    (net (code "39") (name "/RTS") (class "Default")
      (node (ref "Q2") (pin "2") (pinfunction "E_2") (pintype "passive"))
      (node (ref "R29") (pin "1") (pinfunction "1_1") (pintype "passive"))
      (node (ref "U3") (pin "14") (pinfunction "RTS#_14") (pintype "passive"))
    )
    (net (code "40") (name "/RXD") (class "Default")
      (node (ref "R26") (pin "2") (pinfunction "2_2") (pintype "passive"))
      (node (ref "U3") (pin "3") (pinfunction "RXD_3") (pintype "passive"))
    )
    (net (code "41") (name "/SS_NET") (class "Default")
      (node (ref "C10") (pin "2") (pinfunction "2_2") (pintype "passive"))
      (node (ref "U1") (pin "8") (pinfunction "SS_8") (pintype "passive"))
    )
    (net (code "42") (name "/SW_NET") (class "Default")
      (node (ref "C7") (pin "2") (pinfunction "2_2") (pintype "passive"))
      (node (ref "D3") (pin "2") (pinfunction "K_2") (pintype "passive"))
      (node (ref "L1") (pin "1") (pinfunction "1_1") (pintype "passive"))
      (node (ref "U1") (pin "3") (pinfunction "SW_3") (pintype "passive"))
    )
    (net (code "43") (name "/TXD") (class "Default")
      (node (ref "R27") (pin "2") (pinfunction "2_2") (pintype "passive"))
      (node (ref "U3") (pin "2") (pinfunction "TXD_2") (pintype "passive"))
    )
    (net (code "44") (name "/USB_N") (class "Default")
      (node (ref "J1") (pin "A7") (pinfunction "DN1_A7") (pintype "bidirectional"))
      (node (ref "J1") (pin "B7") (pinfunction "DN2_B7") (pintype "bidirectional"))
      (node (ref "U3") (pin "6") (pinfunction "UD-_6") (pintype "passive"))
    )
    (net (code "45") (name "/USB_P") (class "Default")
      (node (ref "J1") (pin "A6") (pinfunction "DP1_A6") (pintype "bidirectional"))
      (node (ref "J1") (pin "B6") (pinfunction "DP2_B6") (pintype "bidirectional"))
      (node (ref "U3") (pin "5") (pinfunction "UD+_5") (pintype "passive"))
    )
    (net (code "46") (name "3.3V") (class "Default")
      (node (ref "C1") (pin "1") (pinfunction "1_1") (pintype "passive"))
      (node (ref "C14") (pin "1") (pinfunction "1_1") (pintype "passive"))
      (node (ref "C15") (pin "1") (pinfunction "1_1") (pintype "passive"))
      (node (ref "C18") (pin "1") (pinfunction "1_1") (pintype "passive"))
      (node (ref "C2") (pin "2") (pinfunction "2_2") (pintype "passive"))
      (node (ref "C21") (pin "1") (pinfunction "1_1") (pintype "passive"))
      (node (ref "C22") (pin "2") (pinfunction "2_2") (pintype "passive"))
      (node (ref "C26") (pin "2") (pinfunction "2_2") (pintype "passive"))
      (node (ref "C27") (pin "2") (pinfunction "2_2") (pintype "passive"))
      (node (ref "C28") (pin "2") (pinfunction "2_2") (pintype "passive"))
      (node (ref "C29") (pin "2") (pinfunction "2_2") (pintype "passive"))
      (node (ref "C3") (pin "1") (pinfunction "1_1") (pintype "passive"))
      (node (ref "C30") (pin "2") (pinfunction "2_2") (pintype "passive"))
      (node (ref "D1") (pin "2") (pinfunction "K_2") (pintype "passive"))
      (node (ref "E1") (pin "1") (pinfunction "1_1") (pintype "passive"))
      (node (ref "ENC1") (pin "4") (pinfunction "4_4") (pintype "passive"))
      (node (ref "ENC2") (pin "4") (pinfunction "4_4") (pintype "passive"))
      (node (ref "ESP") (pin "2") (pinfunction "3V3_2") (pintype "power_in"))
      (node (ref "I1") (pin "0") (pinfunction "VCC_0") (pintype "passive"))
      (node (ref "L1") (pin "2") (pinfunction "2_2") (pintype "passive"))
      (node (ref "L3") (pin "1") (pinfunction "A_1") (pintype "passive"))
      (node (ref "L4") (pin "1") (pinfunction "A_1") (pintype "passive"))
      (node (ref "L5") (pin "1") (pinfunction "A_1") (pintype "passive"))
      (node (ref "R11") (pin "2") (pinfunction "2_2") (pintype "passive"))
      (node (ref "R12") (pin "2") (pinfunction "2_2") (pintype "passive"))
      (node (ref "R21") (pin "1") (pinfunction "1_1") (pintype "passive"))
      (node (ref "R5") (pin "1") (pinfunction "1_1") (pintype "passive"))
      (node (ref "R8") (pin "2") (pinfunction "2_2") (pintype "passive"))
      (node (ref "STM") (pin "1") (pinfunction "VBAT_1") (pintype "passive"))
      (node (ref "STM") (pin "19") (pinfunction "VDD_4_19") (pintype "passive"))
      (node (ref "STM") (pin "32") (pinfunction "VDD_1_32") (pintype "passive"))
      (node (ref "STM") (pin "48") (pinfunction "VDD_2_48") (pintype "passive"))
      (node (ref "STM") (pin "64") (pinfunction "VDD_3_64") (pintype "passive"))
      (node (ref "U3") (pin "16") (pinfunction "VCC_16") (pintype "passive"))
    )
    (net (code "47") (name "8.4V") (class "Default")
      (node (ref "C24") (pin "1") (pinfunction "1_1") (pintype "passive"))
      (node (ref "C25") (pin "2") (pinfunction "2_2") (pintype "passive"))
      (node (ref "C34") (pin "1") (pinfunction "1_1") (pintype "passive"))
      (node (ref "C35") (pin "2") (pinfunction "2_2") (pintype "passive"))
      (node (ref "C4") (pin "1") (pinfunction "1_1") (pintype "passive"))
      (node (ref "C5") (pin "1") (pinfunction "1_1") (pintype "passive"))
      (node (ref "C6") (pin "2") (pinfunction "2_2") (pintype "passive"))
      (node (ref "C9") (pin "1") (pinfunction "1_1") (pintype "passive"))
      (node (ref "D2") (pin "2") (pinfunction "K_2") (pintype "passive"))
      (node (ref "Q1") (pin "2") (pinfunction "S_2") (pintype "passive"))
      (node (ref "R1") (pin "2") (pinfunction "2_2") (pintype "passive"))
      (node (ref "R2") (pin "1") (pinfunction "1_1") (pintype "passive"))
      (node (ref "U1") (pin "2") (pinfunction "IN_2") (pintype "passive"))
      (node (ref "U2") (pin "5") (pinfunction "VM_5") (pintype "input"))
      (node (ref "U4") (pin "5") (pinfunction "VM_5") (pintype "input"))
    )
    (net (code "48") (name "GND") (class "Default")
      (node (ref "BOOT") (pin "1") (pinfunction "1_1") (pintype "passive"))
      (node (ref "C1") (pin "2") (pinfunction "2_2") (pintype "passive"))
      (node (ref "C10") (pin "1") (pinfunction "1_1") (pintype "passive"))
      (node (ref "C11") (pin "2") (pinfunction "2_2") (pintype "passive"))
      (node (ref "C14") (pin "2") (pinfunction "2_2") (pintype "passive"))
      (node (ref "C15") (pin "2") (pinfunction "2_2") (pintype "passive"))
      (node (ref "C16") (pin "1") (pinfunction "1_1") (pintype "passive"))
      (node (ref "C17") (pin "1") (pinfunction "1_1") (pintype "passive"))
      (node (ref "C18") (pin "2") (pinfunction "2_2") (pintype "passive"))
      (node (ref "C19") (pin "2") (pinfunction "2_2") (pintype "passive"))
      (node (ref "C2") (pin "1") (pinfunction "1_1") (pintype "passive"))
      (node (ref "C20") (pin "1") (pinfunction "1_1") (pintype "passive"))
      (node (ref "C21") (pin "2") (pinfunction "2_2") (pintype "passive"))
      (node (ref "C22") (pin "1") (pinfunction "1_1") (pintype "passive"))
      (node (ref "C23") (pin "1") (pinfunction "1_1") (pintype "passive"))
      (node (ref "C24") (pin "2") (pinfunction "2_2") (pintype "passive"))
      (node (ref "C25") (pin "1") (pinfunction "1_1") (pintype "passive"))
      (node (ref "C26") (pin "1") (pinfunction "1_1") (pintype "passive"))
      (node (ref "C27") (pin "1") (pinfunction "1_1") (pintype "passive"))
      (node (ref "C28") (pin "1") (pinfunction "1_1") (pintype "passive"))
      (node (ref "C29") (pin "1") (pinfunction "1_1") (pintype "passive"))
      (node (ref "C3") (pin "2") (pinfunction "2_2") (pintype "passive"))
      (node (ref "C30") (pin "1") (pinfunction "1_1") (pintype "passive"))
      (node (ref "C31") (pin "2") (pinfunction "2_2") (pintype "passive"))
      (node (ref "C32") (pin "2") (pinfunction "2_2") (pintype "passive"))
      (node (ref "C33") (pin "1") (pinfunction "1_1") (pintype "passive"))
      (node (ref "C34") (pin "2") (pinfunction "2_2") (pintype "passive"))
      (node (ref "C35") (pin "1") (pinfunction "1_1") (pintype "passive"))
      (node (ref "C4") (pin "2") (pinfunction "2_2") (pintype "passive"))
      (node (ref "C5") (pin "2") (pinfunction "2_2") (pintype "passive"))
      (node (ref "C6") (pin "1") (pinfunction "1_1") (pintype "passive"))
      (node (ref "C8") (pin "1") (pinfunction "1_1") (pintype "passive"))
      (node (ref "C9") (pin "2") (pinfunction "2_2") (pintype "passive"))
      (node (ref "D1") (pin "1") (pinfunction "A_1") (pintype "passive"))
      (node (ref "D3") (pin "1") (pinfunction "A_1") (pintype "passive"))
      (node (ref "EN") (pin "1") (pinfunction "1_1") (pintype "passive"))
      (node (ref "ENC1") (pin "1") (pinfunction "1_1") (pintype "passive"))
      (node (ref "ENC2") (pin "1") (pinfunction "1_1") (pintype "passive"))
      (node (ref "ESP") (pin "1") (pinfunction "GND_1") (pintype "power_in"))
      (node (ref "ESP") (pin "40") (pinfunction "GND_40") (pintype "power_in"))
      (node (ref "ESP") (pin "41_1") (pinfunction "GND_41_1") (pintype "power_in"))
      (node (ref "ESP") (pin "41_2") (pinfunction "GND_41_2") (pintype "power_in"))
      (node (ref "ESP") (pin "41_3") (pinfunction "GND_41_3") (pintype "power_in"))
      (node (ref "ESP") (pin "41_4") (pinfunction "GND_41_4") (pintype "power_in"))
      (node (ref "ESP") (pin "41_5") (pinfunction "GND_41_5") (pintype "power_in"))
      (node (ref "ESP") (pin "41_6") (pinfunction "GND_41_6") (pintype "power_in"))
      (node (ref "ESP") (pin "41_7") (pinfunction "GND_41_7") (pintype "power_in"))
      (node (ref "ESP") (pin "41_8") (pinfunction "GND_41_8") (pintype "power_in"))
      (node (ref "ESP") (pin "41_9") (pinfunction "GND_41_9") (pintype "power_in"))
      (node (ref "ESP_FLASH") (pin "1") (pinfunction "1_1") (pintype "passive"))
      (node (ref "I1") (pin "1") (pinfunction "GND_1") (pintype "passive"))
      (node (ref "J1") (pin "A1_B12") (pinfunction "GND_A1_B12") (pintype "power_in"))
      (node (ref "J1") (pin "B1_A12") (pinfunction "GND_B1_A12") (pintype "power_in"))
      (node (ref "J1") (pin "S1") (pinfunction "SHIELD_S1") (pintype "passive"))
      (node (ref "J1") (pin "S2") (pinfunction "SHIELD_S2") (pintype "passive"))
      (node (ref "J1") (pin "S3") (pinfunction "SHIELD_S3") (pintype "passive"))
      (node (ref "J1") (pin "S4") (pinfunction "SHIELD_S4") (pintype "passive"))
      (node (ref "JACK DC1") (pin "2") (pinfunction "TN_2") (pintype "passive"))
      (node (ref "L2") (pin "2") (pinfunction "K_2") (pintype "passive"))
      (node (ref "R10") (pin "2") (pinfunction "2_2") (pintype "passive"))
      (node (ref "R18") (pin "1") (pinfunction "1_1") (pintype "passive"))
      (node (ref "R19") (pin "1") (pinfunction "1_1") (pintype "passive"))
      (node (ref "R20") (pin "1") (pinfunction "1_1") (pintype "passive"))
      (node (ref "R22") (pin "2") (pinfunction "2_2") (pintype "passive"))
      (node (ref "R28") (pin "1") (pinfunction "1_1") (pintype "passive"))
      (node (ref "R3") (pin "1") (pinfunction "1_1") (pintype "passive"))
      (node (ref "R4") (pin "1") (pinfunction "1_1") (pintype "passive"))
      (node (ref "R9") (pin "2") (pinfunction "2_2") (pintype "passive"))
      (node (ref "RST") (pin "1") (pinfunction "1_1") (pintype "passive"))
      (node (ref "STM") (pin "12") (pinfunction "VSSA_12") (pintype "passive"))
      (node (ref "STM") (pin "18") (pinfunction "VSS_4_18") (pintype "passive"))
      (node (ref "STM") (pin "31") (pinfunction "VSS_1_31") (pintype "passive"))
      (node (ref "STM") (pin "47") (pinfunction "VSS_2_47") (pintype "passive"))
      (node (ref "STM") (pin "63") (pinfunction "VSS_3_63") (pintype "passive"))
      (node (ref "STM_FLASH") (pin "3") (pinfunction "3_3") (pintype "passive"))
      (node (ref "U1") (pin "4") (pinfunction "GND_4") (pintype "power_in"))
      (node (ref "U1") (pin "EPAD") (pinfunction "EPAD_EPAD") (pintype "passive"))
      (node (ref "U2") (pin "1") (pinfunction "GND_1") (pintype "input"))
      (node (ref "U2") (pin "7") (pinfunction "PGND_7") (pintype "input"))
      (node (ref "U3") (pin "1") (pinfunction "GND_1") (pintype "passive"))
      (node (ref "U4") (pin "1") (pinfunction "GND_1") (pintype "input"))
      (node (ref "U4") (pin "7") (pinfunction "PGND_7") (pintype "input"))
      (node (ref "X1") (pin "2") (pinfunction "2_2") (pintype "passive"))
      (node (ref "X1") (pin "4") (pinfunction "4_4") (pintype "passive"))
    )
    (net (code "49") (name "Net-(BT1-GND)") (class "Default")
      (node (ref "BT1") (pin "2") (pinfunction "GND_2") (pintype "passive"))
      (node (ref "F1") (pin "1") (pinfunction "1_1") (pintype "passive"))
    )
    (net (code "50") (name "Net-(C12-Pad2)") (class "Default")
      (node (ref "C12") (pin "2") (pinfunction "2_2") (pintype "passive"))
      (node (ref "C13") (pin "2") (pinfunction "2_2") (pintype "passive"))
      (node (ref "R9") (pin "1") (pinfunction "1_1") (pintype "passive"))
    )
    (net (code "51") (name "Net-(D2-A)") (class "Default")
      (node (ref "C11") (pin "1") (pinfunction "1_1") (pintype "passive"))
      (node (ref "D2") (pin "1") (pinfunction "A_1") (pintype "passive"))
      (node (ref "Q1") (pin "1") (pinfunction "G_1") (pintype "passive"))
      (node (ref "R4") (pin "2") (pinfunction "2_2") (pintype "passive"))
    )
    (net (code "52") (name "Net-(ESP-IO3)") (class "Default")
      (node (ref "C8") (pin "2") (pinfunction "2_2") (pintype "passive"))
      (node (ref "ESP") (pin "15") (pinfunction "IO3_15") (pintype "bidirectional"))
      (node (ref "R1") (pin "1") (pinfunction "1_1") (pintype "passive"))
      (node (ref "R3") (pin "2") (pinfunction "2_2") (pintype "passive"))
    )
    (net (code "53") (name "Net-(J1-CC1)") (class "Default")
      (node (ref "J1") (pin "A5") (pinfunction "CC1_A5") (pintype "bidirectional"))
      (node (ref "R18") (pin "2") (pinfunction "2_2") (pintype "passive"))
    )
    (net (code "54") (name "Net-(J1-CC2)") (class "Default")
      (node (ref "J1") (pin "B5") (pinfunction "CC2_B5") (pintype "bidirectional"))
      (node (ref "R19") (pin "2") (pinfunction "2_2") (pintype "passive"))
    )
    (net (code "55") (name "Net-(L2-A)") (class "Default")
      (node (ref "L2") (pin "1") (pinfunction "A_1") (pintype "passive"))
      (node (ref "R5") (pin "2") (pinfunction "2_2") (pintype "passive"))
    )
    (net (code "56") (name "Net-(Q1-D)") (class "Default")
      (node (ref "F1") (pin "2") (pinfunction "2_2") (pintype "passive"))
      (node (ref "Q1") (pin "3") (pinfunction "D_3") (pintype "passive"))
    )
    (net (code "57") (name "Net-(Q2-B)") (class "Default")
      (node (ref "Q2") (pin "1") (pinfunction "B_1") (pintype "passive"))
      (node (ref "R23") (pin "2") (pinfunction "2_2") (pintype "passive"))
    )
    (net (code "58") (name "Net-(Q3-B)") (class "Default")
      (node (ref "Q3") (pin "1") (pinfunction "B_1") (pintype "passive"))
      (node (ref "R29") (pin "2") (pinfunction "2_2") (pintype "passive"))
    )
    (net (code "59") (name "Net-(R6-Pad2)") (class "Default")
      (node (ref "R6") (pin "2") (pinfunction "2_2") (pintype "passive"))
      (node (ref "R7") (pin "1") (pinfunction "1_1") (pintype "passive"))
    )
    (net (code "60") (name "Net-(R7-Pad2)") (class "Default")
      (node (ref "R7") (pin "2") (pinfunction "2_2") (pintype "passive"))
      (node (ref "R8") (pin "1") (pinfunction "1_1") (pintype "passive"))
    )
    (net (code "61") (name "Net-(U2-ILIM)") (class "Default")
      (node (ref "R20") (pin "2") (pinfunction "2_2") (pintype "passive"))
      (node (ref "U2") (pin "4") (pinfunction "ILIM_4") (pintype "input"))
    )
    (net (code "62") (name "Net-(U2-IN1)") (class "Default")
      (node (ref "R17") (pin "2") (pinfunction "2_2") (pintype "passive"))
      (node (ref "U2") (pin "3") (pinfunction "IN1_3") (pintype "input"))
    )
    (net (code "63") (name "Net-(U2-IN2)") (class "Default")
      (node (ref "R16") (pin "2") (pinfunction "2_2") (pintype "passive"))
      (node (ref "U2") (pin "2") (pinfunction "IN2_2") (pintype "input"))
    )
    (net (code "64") (name "Net-(U3-V3)") (class "Default")
      (node (ref "C23") (pin "2") (pinfunction "2_2") (pintype "passive"))
      (node (ref "U3") (pin "4") (pinfunction "V3_4") (pintype "passive"))
    )
    (net (code "65") (name "Net-(U4-ILIM)") (class "Default")
      (node (ref "R28") (pin "2") (pinfunction "2_2") (pintype "passive"))
      (node (ref "U4") (pin "4") (pinfunction "ILIM_4") (pintype "input"))
    )
    (net (code "66") (name "Net-(U4-IN1)") (class "Default")
      (node (ref "R25") (pin "2") (pinfunction "2_2") (pintype "passive"))
      (node (ref "U4") (pin "3") (pinfunction "IN1_3") (pintype "input"))
    )
    (net (code "67") (name "Net-(U4-IN2)") (class "Default")
      (node (ref "R24") (pin "2") (pinfunction "2_2") (pintype "passive"))
      (node (ref "U4") (pin "2") (pinfunction "IN2_2") (pintype "input"))
    )
    (net (code "68") (name "VDDA") (class "Default")
      (node (ref "C19") (pin "1") (pinfunction "1_1") (pintype "passive"))
      (node (ref "C20") (pin "2") (pinfunction "2_2") (pintype "passive"))
      (node (ref "E1") (pin "2") (pinfunction "2_2") (pintype "passive"))
      (node (ref "STM") (pin "13") (pinfunction "VDDA_13") (pintype "passive"))
    )
    (net (code "69") (name "VIN") (class "Default")
      (node (ref "BT1") (pin "1") (pinfunction "VCC_1") (pintype "passive"))
      (node (ref "JACK DC1") (pin "1") (pinfunction "T_1") (pintype "passive"))
    )
    (net (code "70") (name "unconnected-(ESP-IO1-Pad39)") (class "Default")
      (node (ref "ESP") (pin "39") (pinfunction "IO1_39") (pintype "bidirectional+no_connect"))
    )
    (net (code "71") (name "unconnected-(ESP-IO2-Pad38)") (class "Default")
      (node (ref "ESP") (pin "38") (pinfunction "IO2_38") (pintype "bidirectional+no_connect"))
    )
    (net (code "72") (name "unconnected-(ESP-IO4-Pad4)") (class "Default")
      (node (ref "ESP") (pin "4") (pinfunction "IO4_4") (pintype "bidirectional+no_connect"))
    )
    (net (code "73") (name "unconnected-(ESP-IO5-Pad5)") (class "Default")
      (node (ref "ESP") (pin "5") (pinfunction "IO5_5") (pintype "bidirectional+no_connect"))
    )
    (net (code "74") (name "unconnected-(ESP-IO6-Pad6)") (class "Default")
      (node (ref "ESP") (pin "6") (pinfunction "IO6_6") (pintype "bidirectional+no_connect"))
    )
    (net (code "75") (name "unconnected-(ESP-IO7-Pad7)") (class "Default")
      (node (ref "ESP") (pin "7") (pinfunction "IO7_7") (pintype "bidirectional+no_connect"))
    )
    (net (code "76") (name "unconnected-(ESP-IO8-Pad12)") (class "Default")
      (node (ref "ESP") (pin "12") (pinfunction "IO8_12") (pintype "bidirectional+no_connect"))
    )
    (net (code "77") (name "unconnected-(ESP-IO9-Pad17)") (class "Default")
      (node (ref "ESP") (pin "17") (pinfunction "IO9_17") (pintype "bidirectional+no_connect"))
    )
    (net (code "78") (name "unconnected-(ESP-IO10-Pad18)") (class "Default")
      (node (ref "ESP") (pin "18") (pinfunction "IO10_18") (pintype "bidirectional+no_connect"))
    )
    (net (code "79") (name "unconnected-(ESP-IO11-Pad19)") (class "Default")
      (node (ref "ESP") (pin "19") (pinfunction "IO11_19") (pintype "bidirectional+no_connect"))
    )
    (net (code "80") (name "unconnected-(ESP-IO12-Pad20)") (class "Default")
      (node (ref "ESP") (pin "20") (pinfunction "IO12_20") (pintype "bidirectional+no_connect"))
    )
    (net (code "81") (name "unconnected-(ESP-IO13-Pad21)") (class "Default")
      (node (ref "ESP") (pin "21") (pinfunction "IO13_21") (pintype "bidirectional+no_connect"))
    )
    (net (code "82") (name "unconnected-(ESP-IO14-Pad22)") (class "Default")
      (node (ref "ESP") (pin "22") (pinfunction "IO14_22") (pintype "bidirectional+no_connect"))
    )
    (net (code "83") (name "unconnected-(ESP-IO15-Pad8)") (class "Default")
      (node (ref "ESP") (pin "8") (pinfunction "IO15_8") (pintype "bidirectional+no_connect"))
    )
    (net (code "84") (name "unconnected-(ESP-IO16-Pad9)") (class "Default")
      (node (ref "ESP") (pin "9") (pinfunction "IO16_9") (pintype "bidirectional+no_connect"))
    )
    (net (code "85") (name "unconnected-(ESP-IO17-Pad10)") (class "Default")
      (node (ref "ESP") (pin "10") (pinfunction "IO17_10") (pintype "bidirectional+no_connect"))
    )
    (net (code "86") (name "unconnected-(ESP-IO18-Pad11)") (class "Default")
      (node (ref "ESP") (pin "11") (pinfunction "IO18_11") (pintype "bidirectional+no_connect"))
    )
    (net (code "87") (name "unconnected-(ESP-IO19-Pad13)") (class "Default")
      (node (ref "ESP") (pin "13") (pinfunction "IO19_13") (pintype "bidirectional+no_connect"))
    )
    (net (code "88") (name "unconnected-(ESP-IO20-Pad14)") (class "Default")
      (node (ref "ESP") (pin "14") (pinfunction "IO20_14") (pintype "bidirectional+no_connect"))
    )
    (net (code "89") (name "unconnected-(ESP-IO21-Pad23)") (class "Default")
      (node (ref "ESP") (pin "23") (pinfunction "IO21_23") (pintype "bidirectional+no_connect"))
    )
    (net (code "90") (name "unconnected-(ESP-IO35-Pad28)") (class "Default")
      (node (ref "ESP") (pin "28") (pinfunction "IO35_28") (pintype "bidirectional+no_connect"))
    )
    (net (code "91") (name "unconnected-(ESP-IO36-Pad29)") (class "Default")
      (node (ref "ESP") (pin "29") (pinfunction "IO36_29") (pintype "bidirectional+no_connect"))
    )
    (net (code "92") (name "unconnected-(ESP-IO37-Pad30)") (class "Default")
      (node (ref "ESP") (pin "30") (pinfunction "IO37_30") (pintype "bidirectional+no_connect"))
    )
    (net (code "93") (name "unconnected-(ESP-IO38-Pad31)") (class "Default")
      (node (ref "ESP") (pin "31") (pinfunction "IO38_31") (pintype "bidirectional+no_connect"))
    )
    (net (code "94") (name "unconnected-(ESP-IO41-Pad34)") (class "Default")
      (node (ref "ESP") (pin "34") (pinfunction "IO41_34") (pintype "bidirectional+no_connect"))
    )
    (net (code "95") (name "unconnected-(ESP-IO42-Pad35)") (class "Default")
      (node (ref "ESP") (pin "35") (pinfunction "IO42_35") (pintype "bidirectional+no_connect"))
    )
    (net (code "96") (name "unconnected-(ESP-IO45-Pad26)") (class "Default")
      (node (ref "ESP") (pin "26") (pinfunction "IO45_26") (pintype "bidirectional+no_connect"))
    )
    (net (code "97") (name "unconnected-(ESP-IO46-Pad16)") (class "Default")
      (node (ref "ESP") (pin "16") (pinfunction "IO46_16") (pintype "bidirectional+no_connect"))
    )
    (net (code "98") (name "unconnected-(ESP-IO47-Pad24)") (class "Default")
      (node (ref "ESP") (pin "24") (pinfunction "IO47_24") (pintype "bidirectional+no_connect"))
    )
    (net (code "99") (name "unconnected-(ESP-IO48-Pad25)") (class "Default")
      (node (ref "ESP") (pin "25") (pinfunction "IO48_25") (pintype "bidirectional+no_connect"))
    )
    (net (code "100") (name "unconnected-(ESP_FLASH-Pad4)") (class "Default")
      (node (ref "ESP_FLASH") (pin "4") (pinfunction "4_4") (pintype "passive+no_connect"))
    )
    (net (code "101") (name "unconnected-(I1-AD0-Pad6)") (class "Default")
      (node (ref "I1") (pin "6") (pinfunction "AD0_6") (pintype "passive+no_connect"))
    )
    (net (code "102") (name "unconnected-(I1-XCL-Pad5)") (class "Default")
      (node (ref "I1") (pin "5") (pinfunction "XCL_5") (pintype "passive+no_connect"))
    )
    (net (code "103") (name "unconnected-(I1-XDA-Pad4)") (class "Default")
      (node (ref "I1") (pin "4") (pinfunction "XDA_4") (pintype "passive+no_connect"))
    )
    (net (code "104") (name "unconnected-(J1-SBU1-PadA8)") (class "Default")
      (node (ref "J1") (pin "A8") (pinfunction "SBU1_A8") (pintype "bidirectional+no_connect"))
    )
    (net (code "105") (name "unconnected-(J1-SBU2-PadB8)") (class "Default")
      (node (ref "J1") (pin "B8") (pinfunction "SBU2_B8") (pintype "bidirectional+no_connect"))
    )
    (net (code "106") (name "unconnected-(J1-VBUS-PadA4_B9)") (class "Default")
      (node (ref "J1") (pin "A4_B9") (pinfunction "VBUS_A4_B9") (pintype "power_in+no_connect"))
    )
    (net (code "107") (name "unconnected-(J1-VBUS-PadB4_A9)") (class "Default")
      (node (ref "J1") (pin "B4_A9") (pinfunction "VBUS_B4_A9") (pintype "power_in+no_connect"))
    )
    (net (code "108") (name "unconnected-(JACK DC1-S-Pad3)") (class "Default")
      (node (ref "JACK DC1") (pin "3") (pinfunction "S_3") (pintype "power_in"))
    )
    (net (code "109") (name "unconnected-(STM-PA0-WKUP-Pad14)") (class "Default")
      (node (ref "STM") (pin "14") (pinfunction "PA0-WKUP_14") (pintype "passive+no_connect"))
    )
    (net (code "110") (name "unconnected-(STM-PA1-Pad15)") (class "Default")
      (node (ref "STM") (pin "15") (pinfunction "PA1_15") (pintype "passive+no_connect"))
    )
    (net (code "111") (name "unconnected-(STM-PA2-Pad16)") (class "Default")
      (node (ref "STM") (pin "16") (pinfunction "PA2_16") (pintype "passive+no_connect"))
    )
    (net (code "112") (name "unconnected-(STM-PA3-Pad17)") (class "Default")
      (node (ref "STM") (pin "17") (pinfunction "PA3_17") (pintype "passive+no_connect"))
    )
    (net (code "113") (name "unconnected-(STM-PA4-Pad20)") (class "Default")
      (node (ref "STM") (pin "20") (pinfunction "PA4_20") (pintype "passive+no_connect"))
    )
    (net (code "114") (name "unconnected-(STM-PA5-Pad21)") (class "Default")
      (node (ref "STM") (pin "21") (pinfunction "PA5_21") (pintype "passive+no_connect"))
    )
    (net (code "115") (name "unconnected-(STM-PA10-Pad43)") (class "Default")
      (node (ref "STM") (pin "43") (pinfunction "PA10_43") (pintype "passive+no_connect"))
    )
    (net (code "116") (name "unconnected-(STM-PA11-Pad44)") (class "Default")
      (node (ref "STM") (pin "44") (pinfunction "PA11_44") (pintype "passive+no_connect"))
    )
    (net (code "117") (name "unconnected-(STM-PA12-Pad45)") (class "Default")
      (node (ref "STM") (pin "45") (pinfunction "PA12_45") (pintype "passive+no_connect"))
    )
    (net (code "118") (name "unconnected-(STM-PB2-Pad28)") (class "Default")
      (node (ref "STM") (pin "28") (pinfunction "PB2_28") (pintype "passive+no_connect"))
    )
    (net (code "119") (name "unconnected-(STM-PB3-Pad55)") (class "Default")
      (node (ref "STM") (pin "55") (pinfunction "PB3_55") (pintype "passive+no_connect"))
    )
    (net (code "120") (name "unconnected-(STM-PB4-Pad56)") (class "Default")
      (node (ref "STM") (pin "56") (pinfunction "PB4_56") (pintype "passive+no_connect"))
    )
    (net (code "121") (name "unconnected-(STM-PB5-Pad57)") (class "Default")
      (node (ref "STM") (pin "57") (pinfunction "PB5_57") (pintype "passive+no_connect"))
    )
    (net (code "122") (name "unconnected-(STM-PB8-Pad61)") (class "Default")
      (node (ref "STM") (pin "61") (pinfunction "PB8_61") (pintype "passive+no_connect"))
    )
    (net (code "123") (name "unconnected-(STM-PB9-Pad62)") (class "Default")
      (node (ref "STM") (pin "62") (pinfunction "PB9_62") (pintype "passive+no_connect"))
    )
    (net (code "124") (name "unconnected-(STM-PB10-Pad29)") (class "Default")
      (node (ref "STM") (pin "29") (pinfunction "PB10_29") (pintype "passive+no_connect"))
    )
    (net (code "125") (name "unconnected-(STM-PB11-Pad30)") (class "Default")
      (node (ref "STM") (pin "30") (pinfunction "PB11_30") (pintype "passive+no_connect"))
    )
    (net (code "126") (name "unconnected-(STM-PB12-Pad33)") (class "Default")
      (node (ref "STM") (pin "33") (pinfunction "PB12_33") (pintype "passive+no_connect"))
    )
    (net (code "127") (name "unconnected-(STM-PB13-Pad34)") (class "Default")
      (node (ref "STM") (pin "34") (pinfunction "PB13_34") (pintype "passive+no_connect"))
    )
    (net (code "128") (name "unconnected-(STM-PB14-Pad35)") (class "Default")
      (node (ref "STM") (pin "35") (pinfunction "PB14_35") (pintype "passive+no_connect"))
    )
    (net (code "129") (name "unconnected-(STM-PB15-Pad36)") (class "Default")
      (node (ref "STM") (pin "36") (pinfunction "PB15_36") (pintype "passive+no_connect"))
    )
    (net (code "130") (name "unconnected-(STM-PC0-Pad8)") (class "Default")
      (node (ref "STM") (pin "8") (pinfunction "PC0_8") (pintype "passive+no_connect"))
    )
    (net (code "131") (name "unconnected-(STM-PC1-Pad9)") (class "Default")
      (node (ref "STM") (pin "9") (pinfunction "PC1_9") (pintype "passive+no_connect"))
    )
    (net (code "132") (name "unconnected-(STM-PC2-Pad10)") (class "Default")
      (node (ref "STM") (pin "10") (pinfunction "PC2_10") (pintype "passive+no_connect"))
    )
    (net (code "133") (name "unconnected-(STM-PC3-Pad11)") (class "Default")
      (node (ref "STM") (pin "11") (pinfunction "PC3_11") (pintype "passive+no_connect"))
    )
    (net (code "134") (name "unconnected-(STM-PC4-Pad24)") (class "Default")
      (node (ref "STM") (pin "24") (pinfunction "PC4_24") (pintype "passive+no_connect"))
    )
    (net (code "135") (name "unconnected-(STM-PC5-Pad25)") (class "Default")
      (node (ref "STM") (pin "25") (pinfunction "PC5_25") (pintype "passive+no_connect"))
    )
    (net (code "136") (name "unconnected-(STM-PC8-Pad39)") (class "Default")
      (node (ref "STM") (pin "39") (pinfunction "PC8_39") (pintype "passive+no_connect"))
    )
    (net (code "137") (name "unconnected-(STM-PC9-Pad40)") (class "Default")
      (node (ref "STM") (pin "40") (pinfunction "PC9_40") (pintype "passive+no_connect"))
    )
    (net (code "138") (name "unconnected-(STM-PC14-OSC32_IN-Pad3)") (class "Default")
      (node (ref "STM") (pin "3") (pinfunction "PC14-OSC32_IN_3") (pintype "passive+no_connect"))
    )
    (net (code "139") (name "unconnected-(STM-PC15-OSC32_OUT-Pad4)") (class "Default")
      (node (ref "STM") (pin "4") (pinfunction "PC15-OSC32_OUT_4") (pintype "passive+no_connect"))
    )
    (net (code "140") (name "unconnected-(STM_FLASH-Pad4)") (class "Default")
      (node (ref "STM_FLASH") (pin "4") (pinfunction "4_4") (pintype "passive+no_connect"))
    )
    (net (code "141") (name "unconnected-(U3-CTS#-Pad9)") (class "Default")
      (node (ref "U3") (pin "9") (pinfunction "CTS#_9") (pintype "passive+no_connect"))
    )
    (net (code "142") (name "unconnected-(U3-DCD#-Pad12)") (class "Default")
      (node (ref "U3") (pin "12") (pinfunction "DCD#_12") (pintype "passive+no_connect"))
    )
    (net (code "143") (name "unconnected-(U3-DSR#-Pad10)") (class "Default")
      (node (ref "U3") (pin "10") (pinfunction "DSR#_10") (pintype "passive+no_connect"))
    )
    (net (code "144") (name "unconnected-(U3-NC-Pad7)") (class "Default")
      (node (ref "U3") (pin "7") (pinfunction "NC_7") (pintype "passive+no_connect"))
    )
    (net (code "145") (name "unconnected-(U3-NC-Pad8)") (class "Default")
      (node (ref "U3") (pin "8") (pinfunction "NC_8") (pintype "passive+no_connect"))
    )
    (net (code "146") (name "unconnected-(U3-R232-Pad15)") (class "Default")
      (node (ref "U3") (pin "15") (pinfunction "R232_15") (pintype "passive+no_connect"))
    )
    (net (code "147") (name "unconnected-(U3-RI#-Pad11)") (class "Default")
      (node (ref "U3") (pin "11") (pinfunction "RI#_11") (pintype "passive+no_connect"))
    )
  )
)
